# CH585D-DG-R0.net
KiCad netlist of a schematic drawn in Altium Designer
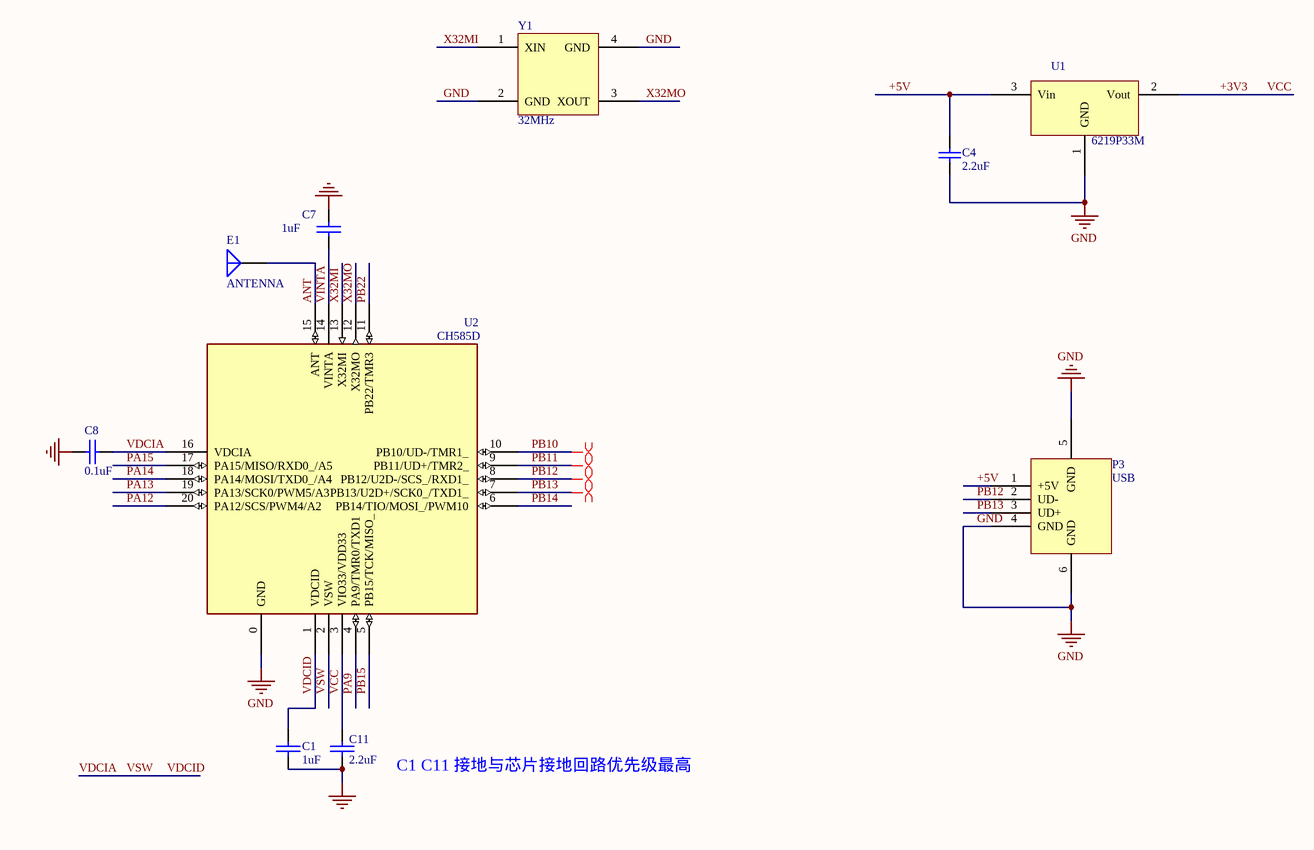
[diagram p0: CH585D-DG-R0.SchDoc]

(export (version "E")
  (design (tool "Eeschema 10.0.6"))
  (components
    (comp (ref "C1")
      (value "1uF")
      (footprint "0402_C")
      (description "Capacitor")
      (libsource (lib "") (part "CAP_1"))
    )
    (comp (ref "C4")
      (value "2.2uF")
      (footprint "0402_C")
      (description "Capacitor")
      (fields (field (name "PUBLISHER") "Altium Limited"))
      (libsource (lib "Miscellaneous Devices") (part "Cap"))
    )
    (comp (ref "C7")
      (value "1uF")
      (footprint "0402_C")
      (description "Capacitor")
      (libsource (lib "*") (part "CAP"))
    )
    (comp (ref "C8")
      (value "0.1uF")
      (footprint "0402_C")
      (description "Capacitor")
      (libsource (lib "*") (part "CAP"))
    )
    (comp (ref "C11")
      (value "2.2uF")
      (footprint "0402_C")
      (description "Capacitor")
      (libsource (lib "*") (part "CAP"))
    )
    (comp (ref "E1")
      (value "ANTENNA")
      (footprint "ANT-F-1-2.4G-0.8mmFR4")
      (description "Generic Antenna")
      (libsource (lib "*") (part "ANTENNA"))
    )
    (comp (ref "P3") (value "USB") (footprint "USBAM-4P") (libsource (lib "Schlib1") (part "USB")))
    (comp (ref "U1")
      (value "6219P33M")
      (footprint "SOT-23")
      (libsource (lib "wch_sch_others") (part "6219P33M"))
    )
    (comp (ref "U2")
      (value "CH585D")
      (footprint "QFN20_3X3")
      (description "RISC-V MCU with BLE/HSUSB/USB/ADC/PWM/SPI/2*UART")
      (libsource (lib "DHXXXSCH") (part "CH585D"))
    )
    (comp (ref "Y1") (value "32MHz") (footprint "XT2016") (libsource (lib "wch_sch_others") (part "晶体")))
  )
  (nets
    (net (code "1") (name "/+3V3") (class "Default")
      (node (ref "C11") (pin "2") (pinfunction "2_2") (pintype "passive"))
      (node (ref "U1") (pin "2") (pinfunction "Vout_2") (pintype "passive"))
      (node (ref "U2") (pin "3") (pinfunction "VIO33/VDD33_3") (pintype "power_in"))
    )
    (net (code "2") (name "/+5V") (class "Default")
      (node (ref "C4") (pin "2") (pinfunction "2_2") (pintype "passive"))
      (node (ref "P3") (pin "1") (pinfunction "+5V_1") (pintype "passive"))
      (node (ref "U1") (pin "3") (pinfunction "Vin_3") (pintype "passive"))
    )
    (net (code "3") (name "/ANT") (class "Default")
      (node (ref "E1") (pin "1") (pinfunction "A_1") (pintype "passive"))
      (node (ref "U2") (pin "15") (pinfunction "ANT_15") (pintype "bidirectional"))
    )
    (net (code "4") (name "/PA9") (class "Default")
      (node (ref "U2") (pin "4") (pinfunction "PA9/TMR0/TXD1_4") (pintype "bidirectional"))
    )
    (net (code "5") (name "/PA12") (class "Default")
      (node (ref "U2") (pin "20") (pinfunction "PA12/SCS/PWM4/A2_20") (pintype "bidirectional"))
    )
    (net (code "6") (name "/PA13") (class "Default")
      (node (ref "U2") (pin "19") (pinfunction "PA13/SCK0/PWM5/A3_19") (pintype "bidirectional"))
    )
    (net (code "7") (name "/PA14") (class "Default")
      (node (ref "U2") (pin "18") (pinfunction "PA14/MOSI/TXD0_/A4_18") (pintype "bidirectional"))
    )
    (net (code "8") (name "/PA15") (class "Default")
      (node (ref "U2") (pin "17") (pinfunction "PA15/MISO/RXD0_/A5_17") (pintype "bidirectional"))
    )
    (net (code "9") (name "/PB10") (class "Default")
      (node (ref "U2") (pin "10") (pinfunction "PB10/UD-/TMR1__10") (pintype "bidirectional"))
    )
    (net (code "10") (name "/PB11") (class "Default")
      (node (ref "U2") (pin "9") (pinfunction "PB11/UD+/TMR2__9") (pintype "bidirectional"))
    )
    (net (code "11") (name "/PB12") (class "Default")
      (node (ref "P3") (pin "2") (pinfunction "UD-_2") (pintype "passive"))
      (node (ref "U2") (pin "8") (pinfunction "PB12/U2D-/SCS_/RXD1__8") (pintype "bidirectional"))
    )
    (net (code "12") (name "/PB13") (class "Default")
      (node (ref "P3") (pin "3") (pinfunction "UD+_3") (pintype "passive"))
      (node (ref "U2") (pin "7") (pinfunction "PB13/U2D+/SCK0_/TXD1__7") (pintype "bidirectional"))
    )
    (net (code "13") (name "/PB14") (class "Default")
      (node (ref "U2") (pin "6") (pinfunction "PB14/TIO/MOSI_/PWM10_6") (pintype "bidirectional"))
    )
    (net (code "14") (name "/PB15") (class "Default")
      (node (ref "U2") (pin "5") (pinfunction "PB15/TCK/MISO__5") (pintype "bidirectional"))
    )
    (net (code "15") (name "/PB22") (class "Default")
      (node (ref "U2") (pin "11") (pinfunction "PB22/TMR3_11") (pintype "bidirectional"))
    )
    (net (code "16") (name "/VDCIA") (class "Default")
      (node (ref "C1") (pin "2") (pinfunction "2_2") (pintype "passive"))
      (node (ref "C8") (pin "1") (pinfunction "1_1") (pintype "passive"))
      (node (ref "U2") (pin "1") (pinfunction "VDCID_1") (pintype "power_in"))
      (node (ref "U2") (pin "16") (pinfunction "VDCIA_16") (pintype "power_in"))
      (node (ref "U2") (pin "2") (pinfunction "VSW_2") (pintype "power_in"))
    )
    (net (code "17") (name "/VINTA") (class "Default")
      (node (ref "C7") (pin "1") (pinfunction "1_1") (pintype "passive"))
      (node (ref "U2") (pin "14") (pinfunction "VINTA_14") (pintype "power_in"))
    )
    (net (code "18") (name "/X32MI") (class "Default")
      (node (ref "U2") (pin "13") (pinfunction "X32MI_13") (pintype "input"))
      (node (ref "Y1") (pin "1") (pinfunction "XIN_1") (pintype "passive"))
    )
    (net (code "19") (name "/X32MO") (class "Default")
      (node (ref "U2") (pin "12") (pinfunction "X32MO_12") (pintype "output"))
      (node (ref "Y1") (pin "3") (pinfunction "XOUT_3") (pintype "passive"))
    )
    (net (code "20") (name "GND") (class "Default")
      (node (ref "C1") (pin "1") (pinfunction "1_1") (pintype "passive"))
      (node (ref "C11") (pin "1") (pinfunction "1_1") (pintype "passive"))
      (node (ref "C4") (pin "1") (pinfunction "1_1") (pintype "passive"))
      (node (ref "C7") (pin "2") (pinfunction "2_2") (pintype "passive"))
      (node (ref "C8") (pin "2") (pinfunction "2_2") (pintype "passive"))
      (node (ref "P3") (pin "4") (pinfunction "GND_4") (pintype "passive"))
      (node (ref "P3") (pin "5") (pinfunction "GND_5") (pintype "passive"))
      (node (ref "P3") (pin "6") (pinfunction "GND_6") (pintype "passive"))
      (node (ref "U1") (pin "1") (pinfunction "GND_1") (pintype "passive"))
      (node (ref "U2") (pin "0") (pinfunction "GND_0") (pintype "power_in"))
      (node (ref "Y1") (pin "2") (pinfunction "GND_2") (pintype "passive"))
      (node (ref "Y1") (pin "4") (pinfunction "GND_4") (pintype "passive"))
    )
  )
)
